# LED_array.net
KiCad netlist of a schematic drawn in EAGLE
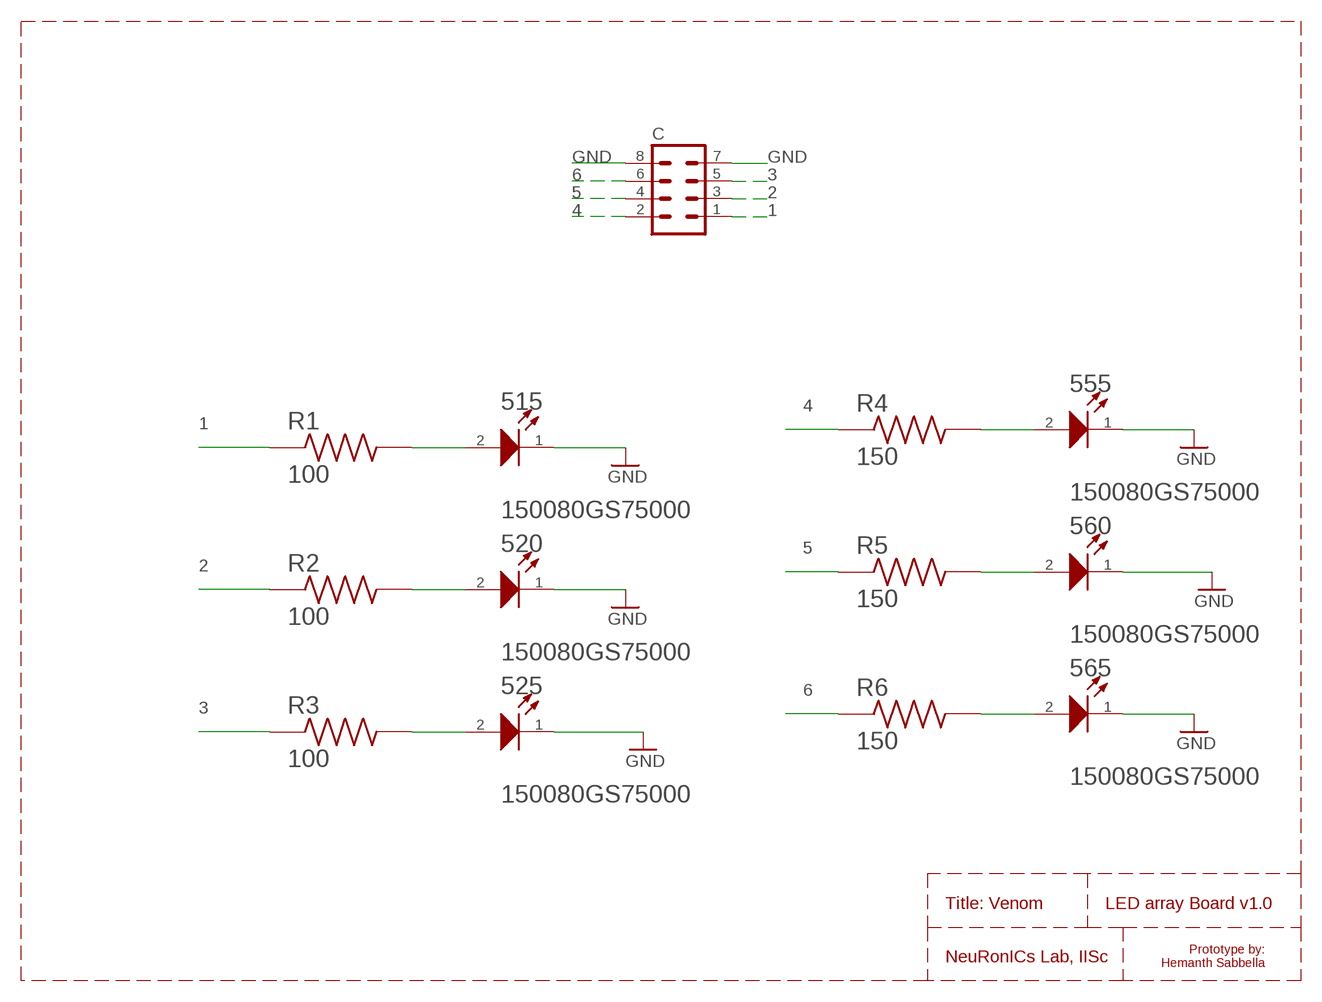
[diagram p0: schematic, sheet 1]

(export (version "E")
  (design (tool "Eeschema 10.0.6"))
  (components
    (comp (ref "515")
      (value "WUERTH_ELEKTRONIK_150080GS75000WUERTH_ELEKTRONIK_150080GS75000_0_0")
      (footprint "eagle-import:WUERTH_ELEKTRONIK_150080GS75000_0")
      (fields (field (name "MF") "Wuerth Elektronik") (field (name "MPN") "150080GS75000"))
      (libsource (lib "eagle-import") (part "WUERTH_ELEKTRONIK_150080GS75000WUERTH_ELEKTRONIK_150080GS75000_0_0"))
    )
    (comp (ref "520")
      (value "WUERTH_ELEKTRONIK_150080GS75000WUERTH_ELEKTRONIK_150080GS75000_0_0")
      (footprint "eagle-import:WUERTH_ELEKTRONIK_150080GS75000_0")
      (fields (field (name "MF") "Wuerth Elektronik") (field (name "MPN") "150080GS75000"))
      (libsource (lib "eagle-import") (part "WUERTH_ELEKTRONIK_150080GS75000WUERTH_ELEKTRONIK_150080GS75000_0_0"))
    )
    (comp (ref "525")
      (value "WUERTH_ELEKTRONIK_150080GS75000WUERTH_ELEKTRONIK_150080GS75000_0_0")
      (footprint "eagle-import:WUERTH_ELEKTRONIK_150080GS75000_0")
      (fields (field (name "MF") "Wuerth Elektronik") (field (name "MPN") "150080GS75000"))
      (libsource (lib "eagle-import") (part "WUERTH_ELEKTRONIK_150080GS75000WUERTH_ELEKTRONIK_150080GS75000_0_0"))
    )
    (comp (ref "555")
      (value "WUERTH_ELEKTRONIK_150080GS75000WUERTH_ELEKTRONIK_150080GS75000_0_0")
      (footprint "eagle-import:WUERTH_ELEKTRONIK_150080GS75000_0")
      (fields (field (name "MF") "Wuerth Elektronik") (field (name "MPN") "150080GS75000"))
      (libsource (lib "eagle-import") (part "WUERTH_ELEKTRONIK_150080GS75000WUERTH_ELEKTRONIK_150080GS75000_0_0"))
    )
    (comp (ref "560")
      (value "WUERTH_ELEKTRONIK_150080GS75000WUERTH_ELEKTRONIK_150080GS75000_0_0")
      (footprint "eagle-import:WUERTH_ELEKTRONIK_150080GS75000_0")
      (fields (field (name "MF") "Wuerth Elektronik") (field (name "MPN") "150080GS75000"))
      (libsource (lib "eagle-import") (part "WUERTH_ELEKTRONIK_150080GS75000WUERTH_ELEKTRONIK_150080GS75000_0_0"))
    )
    (comp (ref "565")
      (value "WUERTH_ELEKTRONIK_150080GS75000WUERTH_ELEKTRONIK_150080GS75000_0_0")
      (footprint "eagle-import:WUERTH_ELEKTRONIK_150080GS75000_0")
      (fields (field (name "MF") "Wuerth Elektronik") (field (name "MPN") "150080GS75000"))
      (libsource (lib "eagle-import") (part "WUERTH_ELEKTRONIK_150080GS75000WUERTH_ELEKTRONIK_150080GS75000_0_0"))
    )
    (comp (ref "C")
      (value "MA04-2")
      (footprint "eagle-import:MA04-2")
      (libsource (lib "eagle-import") (part "MA04-2"))
    )
    (comp (ref "R1")
      (value "100")
      (footprint "eagle-import:RESC3116X65N")
      (fields
        (field (name "DIGI-KEY_PART_NUMBER") "541-10575-1-ND")
        (field (name "MF") "Vishay")
        (field (name "MP") "RCS1206150RFKEA")
      )
      (libsource (lib "eagle-import") (part "RCS1206150RFKEA"))
    )
    (comp (ref "R2")
      (value "100")
      (footprint "eagle-import:RESC3116X65N")
      (fields
        (field (name "DIGI-KEY_PART_NUMBER") "541-10575-1-ND")
        (field (name "MF") "Vishay")
        (field (name "MP") "RCS1206150RFKEA")
      )
      (libsource (lib "eagle-import") (part "RCS1206150RFKEA"))
    )
    (comp (ref "R3")
      (value "100")
      (footprint "eagle-import:RESC3116X65N")
      (fields
        (field (name "DIGI-KEY_PART_NUMBER") "541-10575-1-ND")
        (field (name "MF") "Vishay")
        (field (name "MP") "RCS1206150RFKEA")
      )
      (libsource (lib "eagle-import") (part "RCS1206150RFKEA"))
    )
    (comp (ref "R4")
      (value "150")
      (footprint "eagle-import:RESC3116X65N")
      (fields
        (field (name "DIGI-KEY_PART_NUMBER") "541-10575-1-ND")
        (field (name "MF") "Vishay")
        (field (name "MP") "RCS1206150RFKEA")
      )
      (libsource (lib "eagle-import") (part "RCS1206150RFKEA"))
    )
    (comp (ref "R5")
      (value "150")
      (footprint "eagle-import:RESC3116X65N")
      (fields
        (field (name "DIGI-KEY_PART_NUMBER") "541-10575-1-ND")
        (field (name "MF") "Vishay")
        (field (name "MP") "RCS1206150RFKEA")
      )
      (libsource (lib "eagle-import") (part "RCS1206150RFKEA"))
    )
    (comp (ref "R6")
      (value "150")
      (footprint "eagle-import:RESC3116X65N")
      (fields
        (field (name "DIGI-KEY_PART_NUMBER") "541-10575-1-ND")
        (field (name "MF") "Vishay")
        (field (name "MP") "RCS1206150RFKEA")
      )
      (libsource (lib "eagle-import") (part "RCS1206150RFKEA"))
    )
  )
  (nets
    (net (code "1") (name "/1") (class "Default")
      (node (ref "C") (pin "1") (pinfunction "1_1") (pintype "passive"))
      (node (ref "R1") (pin "1") (pinfunction "1_1") (pintype "passive"))
    )
    (net (code "2") (name "/2") (class "Default")
      (node (ref "C") (pin "3") (pinfunction "3_3") (pintype "passive"))
      (node (ref "R2") (pin "1") (pinfunction "1_1") (pintype "passive"))
    )
    (net (code "3") (name "/3") (class "Default")
      (node (ref "C") (pin "5") (pinfunction "5_5") (pintype "passive"))
      (node (ref "R3") (pin "1") (pinfunction "1_1") (pintype "passive"))
    )
    (net (code "4") (name "/4") (class "Default")
      (node (ref "C") (pin "2") (pinfunction "2_2") (pintype "passive"))
      (node (ref "R4") (pin "1") (pinfunction "1_1") (pintype "passive"))
    )
    (net (code "5") (name "/5") (class "Default")
      (node (ref "C") (pin "4") (pinfunction "4_4") (pintype "passive"))
      (node (ref "R5") (pin "1") (pinfunction "1_1") (pintype "passive"))
    )
    (net (code "6") (name "/6") (class "Default")
      (node (ref "C") (pin "6") (pinfunction "6_6") (pintype "passive"))
      (node (ref "R6") (pin "1") (pinfunction "1_1") (pintype "passive"))
    )
    (net (code "7") (name "GND") (class "Default")
      (node (ref "515") (pin "1") (pinfunction "K_1") (pintype "passive"))
      (node (ref "520") (pin "1") (pinfunction "K_1") (pintype "passive"))
      (node (ref "525") (pin "1") (pinfunction "K_1") (pintype "passive"))
      (node (ref "555") (pin "1") (pinfunction "K_1") (pintype "passive"))
      (node (ref "560") (pin "1") (pinfunction "K_1") (pintype "passive"))
      (node (ref "565") (pin "1") (pinfunction "K_1") (pintype "passive"))
      (node (ref "C") (pin "7") (pinfunction "7_7") (pintype "passive"))
      (node (ref "C") (pin "8") (pinfunction "8_8") (pintype "passive"))
    )
    (net (code "8") (name "Net-(515-A)") (class "Default")
      (node (ref "515") (pin "2") (pinfunction "A_2") (pintype "passive"))
      (node (ref "R1") (pin "2") (pinfunction "2_2") (pintype "passive"))
    )
    (net (code "9") (name "Net-(520-A)") (class "Default")
      (node (ref "520") (pin "2") (pinfunction "A_2") (pintype "passive"))
      (node (ref "R2") (pin "2") (pinfunction "2_2") (pintype "passive"))
    )
    (net (code "10") (name "Net-(525-A)") (class "Default")
      (node (ref "525") (pin "2") (pinfunction "A_2") (pintype "passive"))
      (node (ref "R3") (pin "2") (pinfunction "2_2") (pintype "passive"))
    )
    (net (code "11") (name "Net-(555-A)") (class "Default")
      (node (ref "555") (pin "2") (pinfunction "A_2") (pintype "passive"))
      (node (ref "R4") (pin "2") (pinfunction "2_2") (pintype "passive"))
    )
    (net (code "12") (name "Net-(560-A)") (class "Default")
      (node (ref "560") (pin "2") (pinfunction "A_2") (pintype "passive"))
      (node (ref "R5") (pin "2") (pinfunction "2_2") (pintype "passive"))
    )
    (net (code "13") (name "Net-(565-A)") (class "Default")
      (node (ref "565") (pin "2") (pinfunction "A_2") (pintype "passive"))
      (node (ref "R6") (pin "2") (pinfunction "2_2") (pintype "passive"))
    )
  )
)
